# Sheet1_SchDocEVAL.net
KiCad netlist of a schematic drawn in Altium Designer
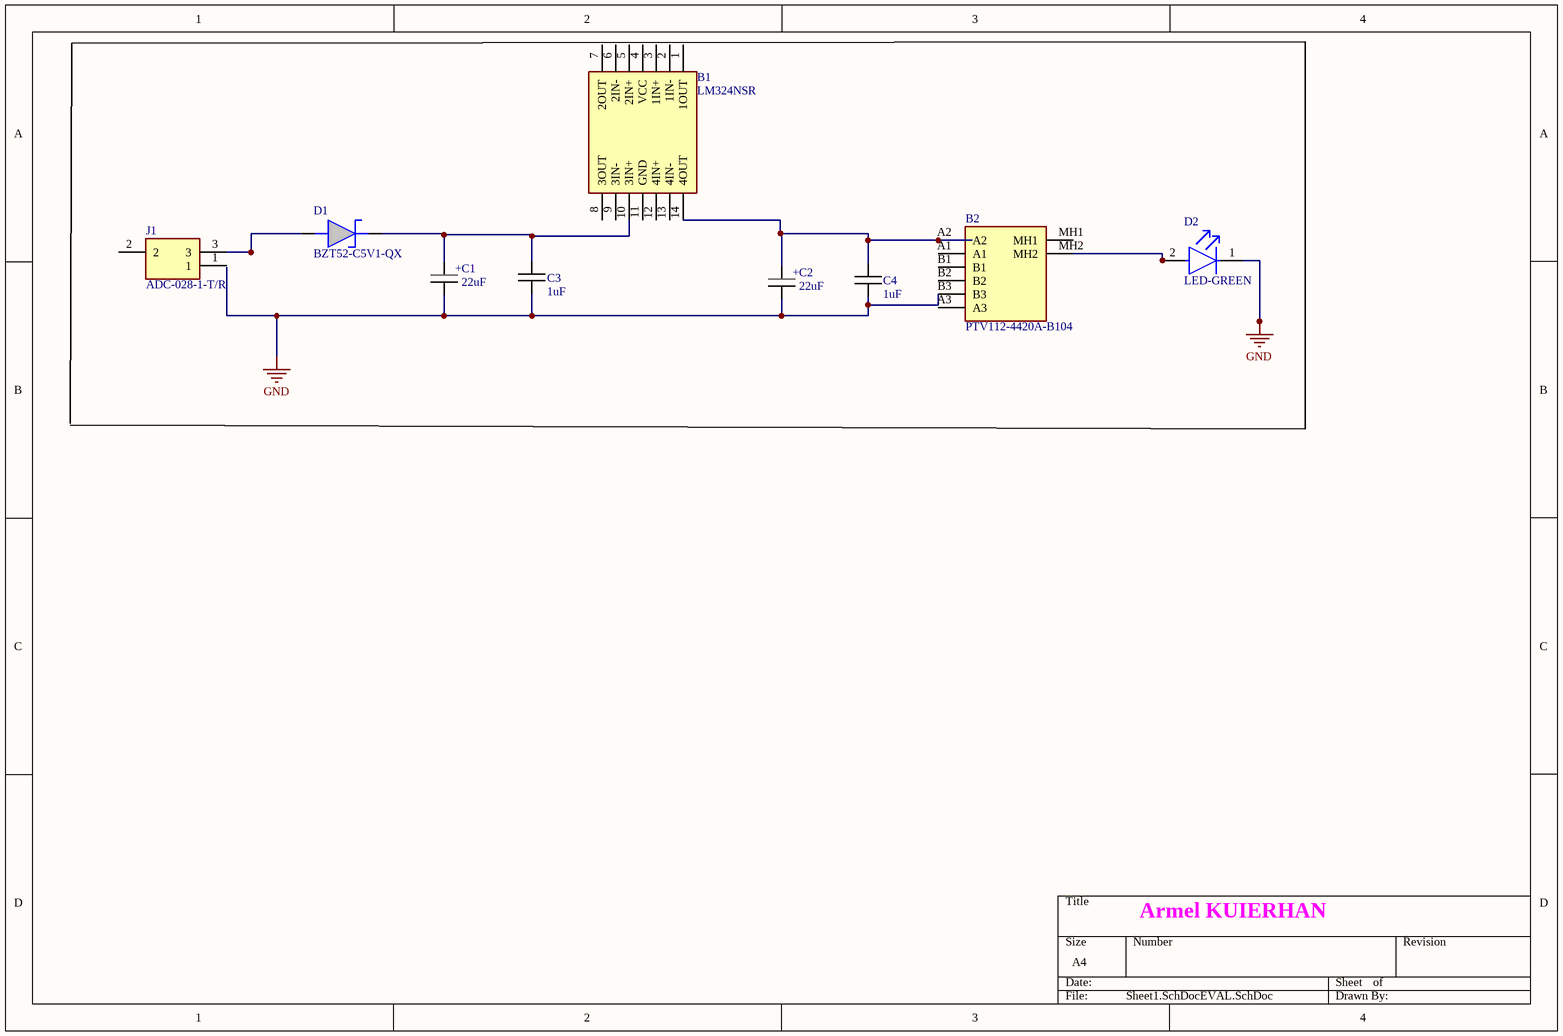
[diagram p0: Sheet1.SchDocEVAL.SchDoc]

(export (version "E")
  (design (tool "Eeschema 10.0.6"))
  (components
    (comp (ref "B1")
      (value "LM324NSR")
      (footprint "SOIC127P780X200-14N")
      (description "Quadruple Operational Amplifier")
      (fields (field (name "MOUSER PART NUMBER") "595-LM324NSR"))
      (libsource (lib "Schlib1") (part "LM324NSR"))
    )
    (comp (ref "B2")
      (value "PTV112-4420A-B104")
      (footprint "PTV1124420AB104")
      (description "Potentiometers PANEL CONTROL 100kOhm")
      (fields (field (name "MOUSER PART NUMBER") "652-PTV1124420AB104"))
      (libsource (lib "Schlib1") (part "PTV112-4420A-B104"))
    )
    (comp (ref "C1")
      (value "22uF")
      (footprint "CAPC1005X06N")
      (libsource (lib "Schlib1") (part "Capacitor_pol"))
    )
    (comp (ref "C2")
      (value "22uF")
      (footprint "CAPC1005X06N")
      (libsource (lib "Schlib1") (part "Capacitor_pol"))
    )
    (comp (ref "C3") (value "1uF") (footprint "CAPC1005X06N") (libsource (lib "Schlib1") (part "Capacitor")))
    (comp (ref "C4") (value "1uF") (footprint "CAPC1005X06N") (libsource (lib "Schlib1") (part "Capacitor")))
    (comp (ref "D1")
      (value "BZT52-C5V1-QX")
      (footprint "SOD3616X130N")
      (description "BZT52-Q series - Voltage regulator diodes@en-us")
      (fields (field (name "MOUSER PART NUMBER") "771-BZT52-C5V1-QX"))
      (libsource (lib "Schlib1") (part "BZT52-C5V1-QX"))
    )
    (comp (ref "D2")
      (value "LED-GREEN")
      (footprint "SMD-1608-LED")
      (description "LED GREEN CLEAR CHIP SMD LTST-C190GKT")
      (fields (field (name "VOLTAGE") "2V"))
      (libsource (lib "Schlib1") (part "LED-GREEN"))
    )
    (comp (ref "J1")
      (value "ADC-028-1-T/R")
      (footprint "PJ1021SMTTR")
      (description "Connecteurs d'alimentation continue DC POWER JACK 2MM PIN TYPE 028")
      (fields (field (name "MOUSER PART NUMBER") "737-ADC-028-1-T/R"))
      (libsource (lib "Schlib1") (part "ADC-028-1-T/R"))
    )
  )
  (nets
    (net (code "1") (name "GND") (class "Default")
      (node (ref "B2") (pin "B3") (pinfunction "B3_B3") (pintype "passive"))
      (node (ref "C1") (pin "2") (pinfunction "2_2") (pintype "passive"))
      (node (ref "C2") (pin "2") (pinfunction "2_2") (pintype "passive"))
      (node (ref "C3") (pin "1") (pinfunction "1_1") (pintype "passive"))
      (node (ref "C4") (pin "1") (pinfunction "1_1") (pintype "passive"))
      (node (ref "D2") (pin "1") (pinfunction "C_1") (pintype "passive"))
    )
    (net (code "2") (name "Net-(B1-3IN+)") (class "Default")
      (node (ref "B1") (pin "10") (pinfunction "3IN+_10") (pintype "passive"))
      (node (ref "C1") (pin "1") (pinfunction "1_1") (pintype "passive"))
      (node (ref "C3") (pin "2") (pinfunction "2_2") (pintype "passive"))
      (node (ref "D1") (pin "1") (pinfunction "K_1") (pintype "passive"))
    )
    (net (code "3") (name "Net-(B1-4OUT)") (class "Default")
      (node (ref "B1") (pin "14") (pinfunction "4OUT_14") (pintype "passive"))
      (node (ref "B2") (pin "A2") (pinfunction "A2_A2") (pintype "passive"))
      (node (ref "C2") (pin "1") (pinfunction "1_1") (pintype "passive"))
      (node (ref "C4") (pin "2") (pinfunction "2_2") (pintype "passive"))
    )
    (net (code "4") (name "Net-(D1-A)") (class "Default")
      (node (ref "D1") (pin "2") (pinfunction "A_2") (pintype "passive"))
      (node (ref "J1") (pin "3") (pinfunction "3_3") (pintype "passive"))
    )
    (net (code "5") (name "Net-(D2-A)") (class "Default")
      (node (ref "B2") (pin "MH2") (pinfunction "MH2_MH2") (pintype "passive"))
      (node (ref "D2") (pin "2") (pinfunction "A_2") (pintype "passive"))
    )
    (net (code "6") (name "unconnected-(B1-1IN+-Pad3)") (class "Default")
      (node (ref "B1") (pin "3") (pinfunction "1IN+_3") (pintype "passive"))
    )
    (net (code "7") (name "unconnected-(B1-1IN--Pad2)") (class "Default")
      (node (ref "B1") (pin "2") (pinfunction "1IN-_2") (pintype "passive"))
    )
    (net (code "8") (name "unconnected-(B1-1OUT-Pad1)") (class "Default")
      (node (ref "B1") (pin "1") (pinfunction "1OUT_1") (pintype "passive"))
    )
    (net (code "9") (name "unconnected-(B1-2IN+-Pad5)") (class "Default")
      (node (ref "B1") (pin "5") (pinfunction "2IN+_5") (pintype "passive"))
    )
    (net (code "10") (name "unconnected-(B1-2IN--Pad6)") (class "Default")
      (node (ref "B1") (pin "6") (pinfunction "2IN-_6") (pintype "passive"))
    )
    (net (code "11") (name "unconnected-(B1-2OUT-Pad7)") (class "Default")
      (node (ref "B1") (pin "7") (pinfunction "2OUT_7") (pintype "passive"))
    )
    (net (code "12") (name "unconnected-(B1-3IN--Pad9)") (class "Default")
      (node (ref "B1") (pin "9") (pinfunction "3IN-_9") (pintype "passive"))
    )
    (net (code "13") (name "unconnected-(B1-3OUT-Pad8)") (class "Default")
      (node (ref "B1") (pin "8") (pinfunction "3OUT_8") (pintype "passive"))
    )
    (net (code "14") (name "unconnected-(B1-4IN+-Pad12)") (class "Default")
      (node (ref "B1") (pin "12") (pinfunction "4IN+_12") (pintype "passive"))
    )
    (net (code "15") (name "unconnected-(B1-4IN--Pad13)") (class "Default")
      (node (ref "B1") (pin "13") (pinfunction "4IN-_13") (pintype "passive"))
    )
    (net (code "16") (name "unconnected-(B1-GND-Pad11)") (class "Default")
      (node (ref "B1") (pin "11") (pinfunction "GND_11") (pintype "passive"))
    )
    (net (code "17") (name "unconnected-(B1-VCC-Pad4)") (class "Default")
      (node (ref "B1") (pin "4") (pinfunction "VCC_4") (pintype "passive"))
    )
    (net (code "18") (name "unconnected-(B2-PadA1)") (class "Default")
      (node (ref "B2") (pin "A1") (pinfunction "A1_A1") (pintype "passive"))
    )
    (net (code "19") (name "unconnected-(B2-PadA3)") (class "Default")
      (node (ref "B2") (pin "A3") (pinfunction "A3_A3") (pintype "passive"))
    )
    (net (code "20") (name "unconnected-(B2-PadB1)") (class "Default")
      (node (ref "B2") (pin "B1") (pinfunction "B1_B1") (pintype "passive"))
    )
    (net (code "21") (name "unconnected-(B2-PadB2)") (class "Default")
      (node (ref "B2") (pin "B2") (pinfunction "B2_B2") (pintype "passive"))
    )
    (net (code "22") (name "unconnected-(B2-PadMH1)") (class "Default")
      (node (ref "B2") (pin "MH1") (pinfunction "MH1_MH1") (pintype "passive"))
    )
    (net (code "23") (name "unconnected-(J1-Pad1)") (class "Default")
      (node (ref "J1") (pin "1") (pinfunction "1_1") (pintype "passive"))
    )
    (net (code "24") (name "unconnected-(J1-Pad2)") (class "Default")
      (node (ref "J1") (pin "2") (pinfunction "2_2") (pintype "passive"))
    )
  )
)
